# coreTwo.net
KiCad netlist of a schematic drawn in EAGLE
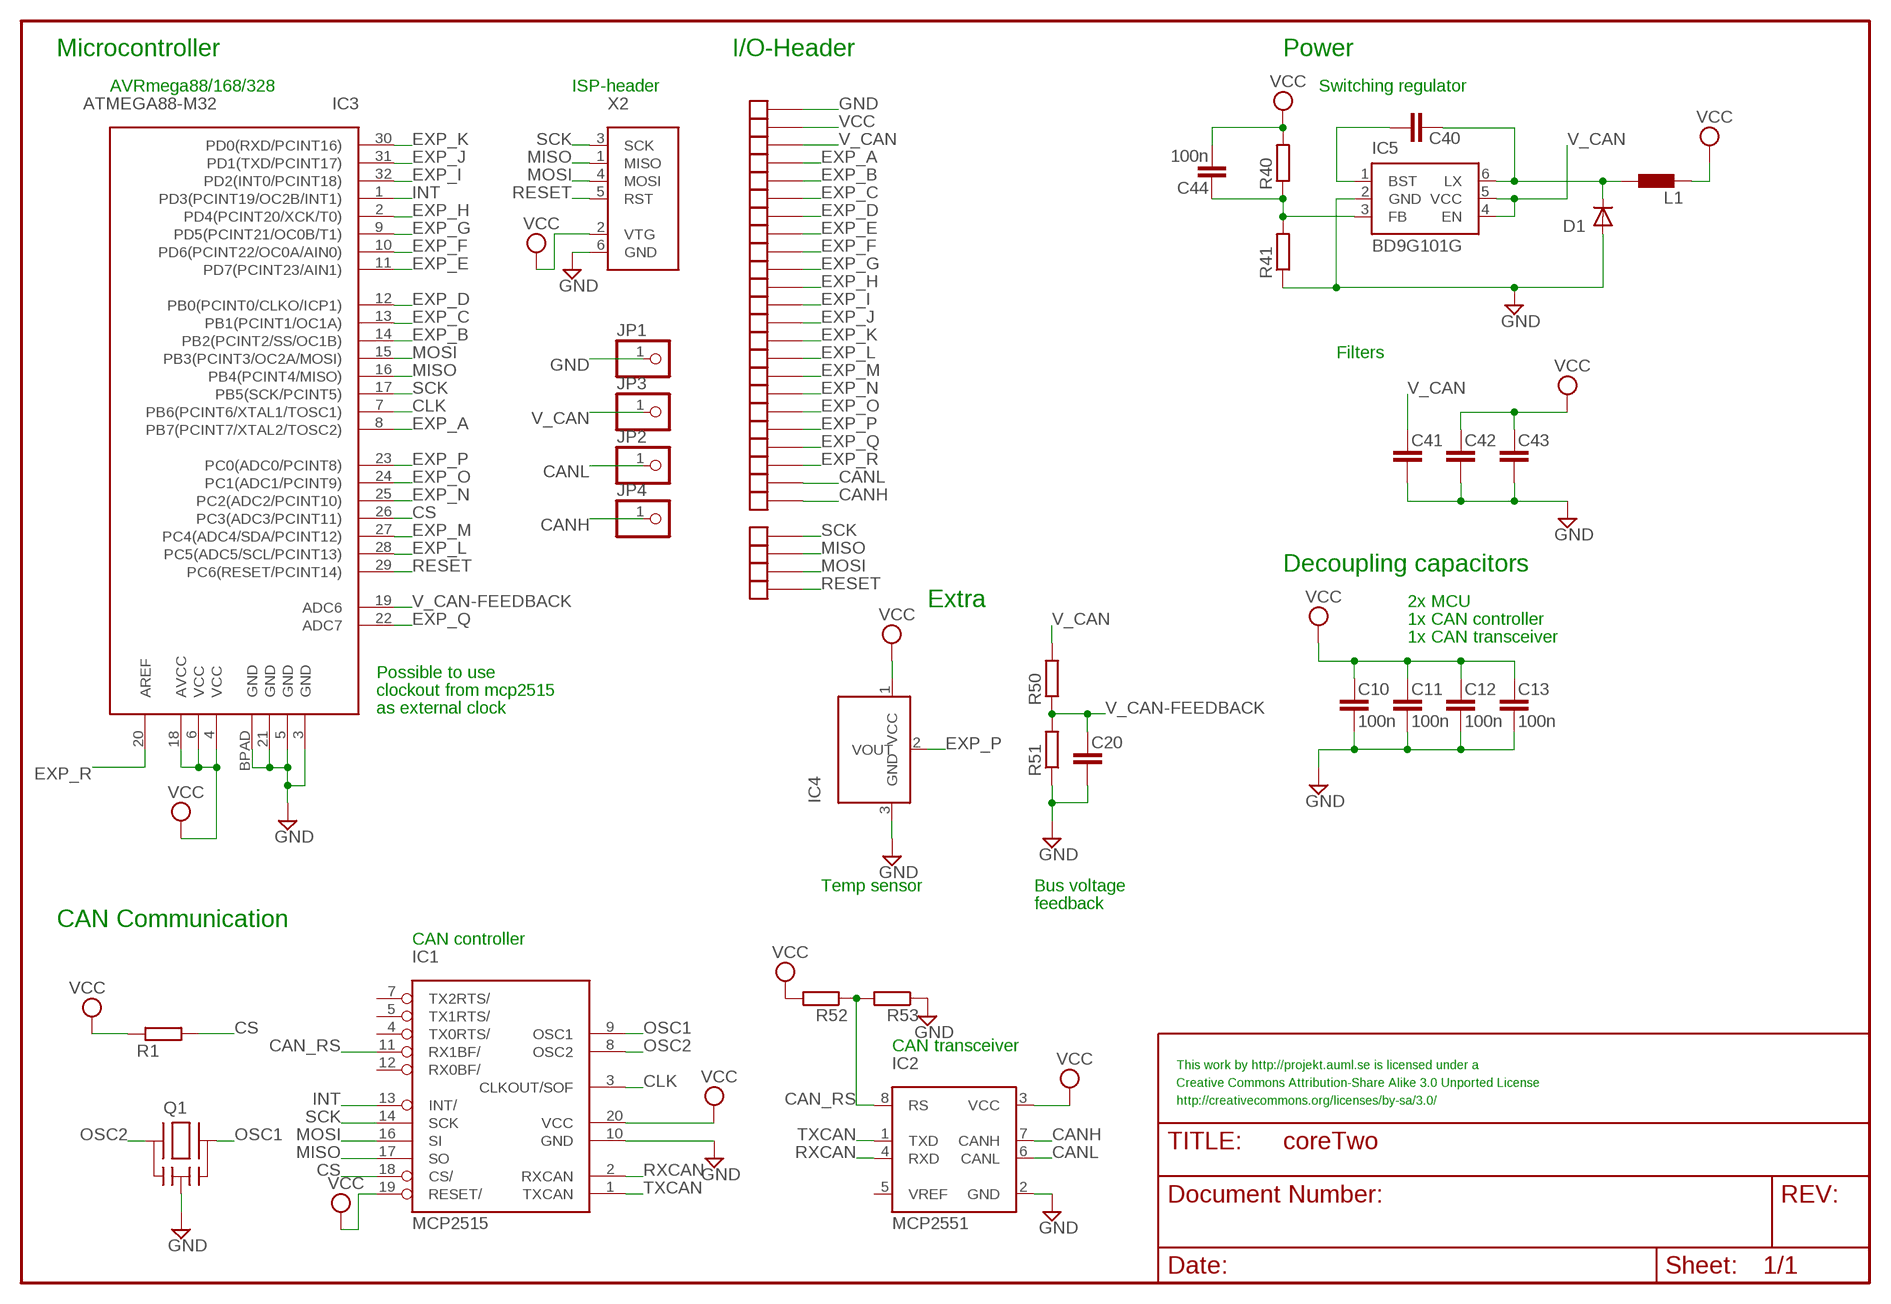
[diagram p0: schematic, sheet 1]

(export (version "E")
  (design (tool "Eeschema 10.0.6"))
  (components
    (comp (ref "C10")
      (value "100n")
      (footprint "eagle-import:C0402")
      (libsource (lib "eagle-import") (part "C-EUC0402"))
    )
    (comp (ref "C11")
      (value "100n")
      (footprint "eagle-import:C0402")
      (libsource (lib "eagle-import") (part "C-EUC0402"))
    )
    (comp (ref "C12")
      (value "100n")
      (footprint "eagle-import:C0402")
      (libsource (lib "eagle-import") (part "C-EUC0402"))
    )
    (comp (ref "C13")
      (value "100n")
      (footprint "eagle-import:C0402")
      (libsource (lib "eagle-import") (part "C-EUC0402"))
    )
    (comp (ref "C20")
      (value "C-EUC0402")
      (footprint "eagle-import:C0402")
      (libsource (lib "eagle-import") (part "C-EUC0402"))
    )
    (comp (ref "C40")
      (value "C-EUC0603")
      (footprint "eagle-import:C0603")
      (libsource (lib "eagle-import") (part "C-EUC0603"))
    )
    (comp (ref "C41")
      (value "C-EUC1210")
      (footprint "eagle-import:C1210")
      (libsource (lib "eagle-import") (part "C-EUC1210"))
    )
    (comp (ref "C42")
      (value "C-EUC0805")
      (footprint "eagle-import:C0805")
      (libsource (lib "eagle-import") (part "C-EUC0805"))
    )
    (comp (ref "C43")
      (value "C-EUC0402")
      (footprint "eagle-import:C0402")
      (libsource (lib "eagle-import") (part "C-EUC0402"))
    )
    (comp (ref "C44")
      (value "100n")
      (footprint "eagle-import:C0402")
      (libsource (lib "eagle-import") (part "C-EUC0402"))
    )
    (comp (ref "CANH")
      (value "CORETWO_PIN")
      (footprint "eagle-import:CORETWO_PIN")
      (libsource (lib "eagle-import") (part "CORETWO_PIN"))
    )
    (comp (ref "CANL")
      (value "CORETWO_PIN")
      (footprint "eagle-import:CORETWO_PIN")
      (libsource (lib "eagle-import") (part "CORETWO_PIN"))
    )
    (comp (ref "D1")
      (value "DIODESMP")
      (footprint "eagle-import:DO-220AA")
      (libsource (lib "eagle-import") (part "DIODESMP"))
    )
    (comp (ref "EXP_A")
      (value "CORETWO_PIN")
      (footprint "eagle-import:CORETWO_PIN")
      (libsource (lib "eagle-import") (part "CORETWO_PIN"))
    )
    (comp (ref "EXP_B")
      (value "CORETWO_PIN")
      (footprint "eagle-import:CORETWO_PIN")
      (libsource (lib "eagle-import") (part "CORETWO_PIN"))
    )
    (comp (ref "EXP_C")
      (value "CORETWO_PIN")
      (footprint "eagle-import:CORETWO_PIN")
      (libsource (lib "eagle-import") (part "CORETWO_PIN"))
    )
    (comp (ref "EXP_D")
      (value "CORETWO_PIN")
      (footprint "eagle-import:CORETWO_PIN")
      (libsource (lib "eagle-import") (part "CORETWO_PIN"))
    )
    (comp (ref "EXP_E")
      (value "CORETWO_PIN")
      (footprint "eagle-import:CORETWO_PIN")
      (libsource (lib "eagle-import") (part "CORETWO_PIN"))
    )
    (comp (ref "EXP_F")
      (value "CORETWO_PIN")
      (footprint "eagle-import:CORETWO_PIN")
      (libsource (lib "eagle-import") (part "CORETWO_PIN"))
    )
    (comp (ref "EXP_G")
      (value "CORETWO_PIN")
      (footprint "eagle-import:CORETWO_PIN")
      (libsource (lib "eagle-import") (part "CORETWO_PIN"))
    )
    (comp (ref "EXP_H")
      (value "CORETWO_PIN")
      (footprint "eagle-import:CORETWO_PIN")
      (libsource (lib "eagle-import") (part "CORETWO_PIN"))
    )
    (comp (ref "EXP_I")
      (value "CORETWO_PIN")
      (footprint "eagle-import:CORETWO_PIN")
      (libsource (lib "eagle-import") (part "CORETWO_PIN"))
    )
    (comp (ref "EXP_J")
      (value "CORETWO_PIN")
      (footprint "eagle-import:CORETWO_PIN")
      (libsource (lib "eagle-import") (part "CORETWO_PIN"))
    )
    (comp (ref "EXP_K")
      (value "CORETWO_PIN")
      (footprint "eagle-import:CORETWO_PIN")
      (libsource (lib "eagle-import") (part "CORETWO_PIN"))
    )
    (comp (ref "EXP_L")
      (value "CORETWO_PIN")
      (footprint "eagle-import:CORETWO_PIN")
      (libsource (lib "eagle-import") (part "CORETWO_PIN"))
    )
    (comp (ref "EXP_M")
      (value "CORETWO_PIN")
      (footprint "eagle-import:CORETWO_PIN")
      (libsource (lib "eagle-import") (part "CORETWO_PIN"))
    )
    (comp (ref "EXP_N")
      (value "CORETWO_PIN")
      (footprint "eagle-import:CORETWO_PIN")
      (libsource (lib "eagle-import") (part "CORETWO_PIN"))
    )
    (comp (ref "EXP_O")
      (value "CORETWO_PIN")
      (footprint "eagle-import:CORETWO_PIN")
      (libsource (lib "eagle-import") (part "CORETWO_PIN"))
    )
    (comp (ref "EXP_P")
      (value "CORETWO_PIN")
      (footprint "eagle-import:CORETWO_PIN")
      (libsource (lib "eagle-import") (part "CORETWO_PIN"))
    )
    (comp (ref "EXP_Q")
      (value "CORETWO_PIN")
      (footprint "eagle-import:CORETWO_PIN")
      (libsource (lib "eagle-import") (part "CORETWO_PIN"))
    )
    (comp (ref "EXP_R")
      (value "CORETWO_PIN")
      (footprint "eagle-import:CORETWO_PIN")
      (libsource (lib "eagle-import") (part "CORETWO_PIN"))
    )
    (comp (ref "GND")
      (value "CORETWO_PIN")
      (footprint "eagle-import:CORETWO_PIN")
      (libsource (lib "eagle-import") (part "CORETWO_PIN"))
    )
    (comp (ref "IC1")
      (value "MCP2515")
      (footprint "eagle-import:TSSOP")
      (libsource (lib "eagle-import") (part "MCP2515"))
    )
    (comp (ref "IC2")
      (value "MCP2551")
      (footprint "eagle-import:SOIC")
      (libsource (lib "eagle-import") (part "MCP2551"))
    )
    (comp (ref "IC3")
      (value "ATMEGA88-M32")
      (footprint "eagle-import:MLF32")
      (libsource (lib "eagle-import") (part "ATMEGA88-M32"))
    )
    (comp (ref "IC4")
      (value "TC1047A")
      (footprint "eagle-import:SOT23")
      (libsource (lib "eagle-import") (part "TC1047A"))
    )
    (comp (ref "IC5")
      (value "BD9G101G")
      (footprint "eagle-import:SSOP6")
      (libsource (lib "eagle-import") (part "BD9G101G"))
    )
    (comp (ref "JP1")
      (value "PINHD-1X1SMD")
      (footprint "eagle-import:1X01_SMD")
      (libsource (lib "eagle-import") (part "PINHD-1X1SMD"))
    )
    (comp (ref "JP2")
      (value "PINHD-1X1SMD")
      (footprint "eagle-import:1X01_SMD")
      (libsource (lib "eagle-import") (part "PINHD-1X1SMD"))
    )
    (comp (ref "JP3")
      (value "PINHD-1X1SMD")
      (footprint "eagle-import:1X01_SMD")
      (libsource (lib "eagle-import") (part "PINHD-1X1SMD"))
    )
    (comp (ref "JP4")
      (value "PINHD-1X1SMD")
      (footprint "eagle-import:1X01_SMD")
      (libsource (lib "eagle-import") (part "PINHD-1X1SMD"))
    )
    (comp (ref "L1")
      (value "L-EUL1210")
      (footprint "eagle-import:L1210")
      (libsource (lib "eagle-import") (part "L-EUL1210"))
    )
    (comp (ref "MISO")
      (value "CORETWO_PIN")
      (footprint "eagle-import:CORETWO_PIN")
      (libsource (lib "eagle-import") (part "CORETWO_PIN"))
    )
    (comp (ref "MOSI")
      (value "CORETWO_PIN")
      (footprint "eagle-import:CORETWO_PIN")
      (libsource (lib "eagle-import") (part "CORETWO_PIN"))
    )
    (comp (ref "Q1")
      (value "CSTCESMD")
      (footprint "eagle-import:SMD")
      (libsource (lib "eagle-import") (part "CSTCESMD"))
    )
    (comp (ref "R1")
      (value "R-EUR0402")
      (footprint "eagle-import:R0402")
      (libsource (lib "eagle-import") (part "R-EUR0402"))
    )
    (comp (ref "R40")
      (value "R-EUR0402")
      (footprint "eagle-import:R0402")
      (libsource (lib "eagle-import") (part "R-EUR0402"))
    )
    (comp (ref "R41")
      (value "R-EUR0402")
      (footprint "eagle-import:R0402")
      (libsource (lib "eagle-import") (part "R-EUR0402"))
    )
    (comp (ref "R50")
      (value "R-EUR0402")
      (footprint "eagle-import:R0402")
      (libsource (lib "eagle-import") (part "R-EUR0402"))
    )
    (comp (ref "R51")
      (value "R-EUR0402")
      (footprint "eagle-import:R0402")
      (libsource (lib "eagle-import") (part "R-EUR0402"))
    )
    (comp (ref "R52")
      (value "R-EUR0402")
      (footprint "eagle-import:R0402")
      (libsource (lib "eagle-import") (part "R-EUR0402"))
    )
    (comp (ref "R53")
      (value "R-EUR0402")
      (footprint "eagle-import:R0402")
      (libsource (lib "eagle-import") (part "R-EUR0402"))
    )
    (comp (ref "RST")
      (value "CORETWO_PIN")
      (footprint "eagle-import:CORETWO_PIN")
      (libsource (lib "eagle-import") (part "CORETWO_PIN"))
    )
    (comp (ref "SCK")
      (value "CORETWO_PIN")
      (footprint "eagle-import:CORETWO_PIN")
      (libsource (lib "eagle-import") (part "CORETWO_PIN"))
    )
    (comp (ref "VCC")
      (value "CORETWO_PIN")
      (footprint "eagle-import:CORETWO_PIN")
      (libsource (lib "eagle-import") (part "CORETWO_PIN"))
    )
    (comp (ref "V_CAN")
      (value "CORETWO_PIN")
      (footprint "eagle-import:CORETWO_PIN")
      (libsource (lib "eagle-import") (part "CORETWO_PIN"))
    )
    (comp (ref "X2")
      (value "AVRISP6PIN")
      (footprint "eagle-import:6PINSMD")
      (libsource (lib "eagle-import") (part "AVRISP6PIN"))
    )
  )
  (nets
    (net (code "1") (name "/CANH") (class "Default")
      (node (ref "CANH") (pin "1") (pinfunction "EXP__1") (pintype "bidirectional"))
      (node (ref "IC2") (pin "7") (pinfunction "CANH_7") (pintype "bidirectional"))
      (node (ref "JP4") (pin "1") (pinfunction "1_1") (pintype "passive"))
    )
    (net (code "2") (name "/CANL") (class "Default")
      (node (ref "CANL") (pin "1") (pinfunction "EXP__1") (pintype "bidirectional"))
      (node (ref "IC2") (pin "6") (pinfunction "CANL_6") (pintype "bidirectional"))
      (node (ref "JP2") (pin "1") (pinfunction "1_1") (pintype "passive"))
    )
    (net (code "3") (name "/CAN_RS") (class "Default")
      (node (ref "IC1") (pin "11") (pinfunction "RX1BF/_11") (pintype "bidirectional"))
      (node (ref "IC2") (pin "8") (pinfunction "RS_8") (pintype "bidirectional"))
      (node (ref "R52") (pin "1") (pinfunction "1_1") (pintype "passive"))
      (node (ref "R53") (pin "2") (pinfunction "2_2") (pintype "passive"))
    )
    (net (code "4") (name "/CLK") (class "Default")
      (node (ref "IC1") (pin "3") (pinfunction "CLKOUT/SOF_3") (pintype "bidirectional"))
      (node (ref "IC3") (pin "7") (pinfunction "PB6(PCINT6/XTAL1/TOSC1)_7") (pintype "bidirectional"))
    )
    (net (code "5") (name "/CS") (class "Default")
      (node (ref "IC1") (pin "18") (pinfunction "CS/_18") (pintype "input"))
      (node (ref "IC3") (pin "26") (pinfunction "PC3(ADC3/PCINT11)_26") (pintype "bidirectional"))
      (node (ref "R1") (pin "2") (pinfunction "2_2") (pintype "passive"))
    )
    (net (code "6") (name "/EXP_A") (class "Default")
      (node (ref "EXP_A") (pin "1") (pinfunction "EXP__1") (pintype "bidirectional"))
      (node (ref "IC3") (pin "8") (pinfunction "PB7(PCINT7/XTAL2/TOSC2)_8") (pintype "bidirectional"))
    )
    (net (code "7") (name "/EXP_B") (class "Default")
      (node (ref "EXP_B") (pin "1") (pinfunction "EXP__1") (pintype "bidirectional"))
      (node (ref "IC3") (pin "14") (pinfunction "PB2(PCINT2/SS/OC1B)_14") (pintype "bidirectional"))
    )
    (net (code "8") (name "/EXP_C") (class "Default")
      (node (ref "EXP_C") (pin "1") (pinfunction "EXP__1") (pintype "bidirectional"))
      (node (ref "IC3") (pin "13") (pinfunction "PB1(PCINT1/OC1A)_13") (pintype "bidirectional"))
    )
    (net (code "9") (name "/EXP_D") (class "Default")
      (node (ref "EXP_D") (pin "1") (pinfunction "EXP__1") (pintype "bidirectional"))
      (node (ref "IC3") (pin "12") (pinfunction "PB0(PCINT0/CLKO/ICP1)_12") (pintype "bidirectional"))
    )
    (net (code "10") (name "/EXP_E") (class "Default")
      (node (ref "EXP_E") (pin "1") (pinfunction "EXP__1") (pintype "bidirectional"))
      (node (ref "IC3") (pin "11") (pinfunction "PD7(PCINT23/AIN1)_11") (pintype "bidirectional"))
    )
    (net (code "11") (name "/EXP_F") (class "Default")
      (node (ref "EXP_F") (pin "1") (pinfunction "EXP__1") (pintype "bidirectional"))
      (node (ref "IC3") (pin "10") (pinfunction "PD6(PCINT22/OC0A/AIN0)_10") (pintype "bidirectional"))
    )
    (net (code "12") (name "/EXP_G") (class "Default")
      (node (ref "EXP_G") (pin "1") (pinfunction "EXP__1") (pintype "bidirectional"))
      (node (ref "IC3") (pin "9") (pinfunction "PD5(PCINT21/OC0B/T1)_9") (pintype "bidirectional"))
    )
    (net (code "13") (name "/EXP_H") (class "Default")
      (node (ref "EXP_H") (pin "1") (pinfunction "EXP__1") (pintype "bidirectional"))
      (node (ref "IC3") (pin "2") (pinfunction "PD4(PCINT20/XCK/T0)_2") (pintype "bidirectional"))
    )
    (net (code "14") (name "/EXP_I") (class "Default")
      (node (ref "EXP_I") (pin "1") (pinfunction "EXP__1") (pintype "bidirectional"))
      (node (ref "IC3") (pin "32") (pinfunction "PD2(INT0/PCINT18)_32") (pintype "bidirectional"))
    )
    (net (code "15") (name "/EXP_J") (class "Default")
      (node (ref "EXP_J") (pin "1") (pinfunction "EXP__1") (pintype "bidirectional"))
      (node (ref "IC3") (pin "31") (pinfunction "PD1(TXD/PCINT17)_31") (pintype "bidirectional"))
    )
    (net (code "16") (name "/EXP_K") (class "Default")
      (node (ref "EXP_K") (pin "1") (pinfunction "EXP__1") (pintype "bidirectional"))
      (node (ref "IC3") (pin "30") (pinfunction "PD0(RXD/PCINT16)_30") (pintype "bidirectional"))
    )
    (net (code "17") (name "/EXP_L") (class "Default")
      (node (ref "EXP_L") (pin "1") (pinfunction "EXP__1") (pintype "bidirectional"))
      (node (ref "IC3") (pin "28") (pinfunction "PC5(ADC5/SCL/PCINT13)_28") (pintype "bidirectional"))
    )
    (net (code "18") (name "/EXP_M") (class "Default")
      (node (ref "EXP_M") (pin "1") (pinfunction "EXP__1") (pintype "bidirectional"))
      (node (ref "IC3") (pin "27") (pinfunction "PC4(ADC4/SDA/PCINT12)_27") (pintype "bidirectional"))
    )
    (net (code "19") (name "/EXP_N") (class "Default")
      (node (ref "EXP_N") (pin "1") (pinfunction "EXP__1") (pintype "bidirectional"))
      (node (ref "IC3") (pin "25") (pinfunction "PC2(ADC2/PCINT10)_25") (pintype "bidirectional"))
    )
    (net (code "20") (name "/EXP_O") (class "Default")
      (node (ref "EXP_O") (pin "1") (pinfunction "EXP__1") (pintype "bidirectional"))
      (node (ref "IC3") (pin "24") (pinfunction "PC1(ADC1/PCINT9)_24") (pintype "bidirectional"))
    )
    (net (code "21") (name "/EXP_P") (class "Default")
      (node (ref "EXP_P") (pin "1") (pinfunction "EXP__1") (pintype "bidirectional"))
      (node (ref "IC3") (pin "23") (pinfunction "PC0(ADC0/PCINT8)_23") (pintype "bidirectional"))
      (node (ref "IC4") (pin "2") (pinfunction "VOUT_2") (pintype "output"))
    )
    (net (code "22") (name "/EXP_Q") (class "Default")
      (node (ref "EXP_Q") (pin "1") (pinfunction "EXP__1") (pintype "bidirectional"))
      (node (ref "IC3") (pin "22") (pinfunction "ADC7_22") (pintype "bidirectional"))
    )
    (net (code "23") (name "/EXP_R") (class "Default")
      (node (ref "EXP_R") (pin "1") (pinfunction "EXP__1") (pintype "bidirectional"))
      (node (ref "IC3") (pin "20") (pinfunction "AREF_20") (pintype "passive"))
    )
    (net (code "24") (name "/INT") (class "Default")
      (node (ref "IC1") (pin "13") (pinfunction "INT/_13") (pintype "output"))
      (node (ref "IC3") (pin "1") (pinfunction "PD3(PCINT19/OC2B/INT1)_1") (pintype "bidirectional"))
    )
    (net (code "25") (name "/MISO") (class "Default")
      (node (ref "IC1") (pin "17") (pinfunction "SO_17") (pintype "output"))
      (node (ref "IC3") (pin "16") (pinfunction "PB4(PCINT4/MISO)_16") (pintype "bidirectional"))
      (node (ref "MISO") (pin "1") (pinfunction "EXP__1") (pintype "bidirectional"))
      (node (ref "X2") (pin "1") (pinfunction "MISO_1") (pintype "bidirectional"))
    )
    (net (code "26") (name "/MOSI") (class "Default")
      (node (ref "IC1") (pin "16") (pinfunction "SI_16") (pintype "input"))
      (node (ref "IC3") (pin "15") (pinfunction "PB3(PCINT3/OC2A/MOSI)_15") (pintype "bidirectional"))
      (node (ref "MOSI") (pin "1") (pinfunction "EXP__1") (pintype "bidirectional"))
      (node (ref "X2") (pin "4") (pinfunction "MOSI_4") (pintype "bidirectional"))
    )
    (net (code "27") (name "/OSC1") (class "Default")
      (node (ref "IC1") (pin "9") (pinfunction "OSC1_9") (pintype "bidirectional"))
      (node (ref "Q1") (pin "3") (pinfunction "2_3") (pintype "bidirectional"))
    )
    (net (code "28") (name "/OSC2") (class "Default")
      (node (ref "IC1") (pin "8") (pinfunction "OSC2_8") (pintype "bidirectional"))
      (node (ref "Q1") (pin "1") (pinfunction "1_1") (pintype "bidirectional"))
    )
    (net (code "29") (name "/RESET") (class "Default")
      (node (ref "IC3") (pin "29") (pinfunction "PC6(RESET/PCINT14)_29") (pintype "bidirectional"))
      (node (ref "RST") (pin "1") (pinfunction "EXP__1") (pintype "bidirectional"))
      (node (ref "X2") (pin "5") (pinfunction "RST_5") (pintype "bidirectional"))
    )
    (net (code "30") (name "/RXCAN") (class "Default")
      (node (ref "IC1") (pin "2") (pinfunction "RXCAN_2") (pintype "bidirectional"))
      (node (ref "IC2") (pin "4") (pinfunction "RXD_4") (pintype "bidirectional"))
    )
    (net (code "31") (name "/SCK") (class "Default")
      (node (ref "IC1") (pin "14") (pinfunction "SCK_14") (pintype "input"))
      (node (ref "IC3") (pin "17") (pinfunction "PB5(SCK/PCINT5)_17") (pintype "bidirectional"))
      (node (ref "SCK") (pin "1") (pinfunction "EXP__1") (pintype "bidirectional"))
      (node (ref "X2") (pin "3") (pinfunction "SCK_3") (pintype "bidirectional"))
    )
    (net (code "32") (name "/TXCAN") (class "Default")
      (node (ref "IC1") (pin "1") (pinfunction "TXCAN_1") (pintype "bidirectional"))
      (node (ref "IC2") (pin "1") (pinfunction "TXD_1") (pintype "bidirectional"))
    )
    (net (code "33") (name "/V_CAN") (class "Default")
      (node (ref "C41") (pin "1") (pinfunction "1_1") (pintype "passive"))
      (node (ref "IC5") (pin "4") (pinfunction "EN_4") (pintype "bidirectional"))
      (node (ref "IC5") (pin "5") (pinfunction "VCC_5") (pintype "bidirectional"))
      (node (ref "JP3") (pin "1") (pinfunction "1_1") (pintype "passive"))
      (node (ref "R50") (pin "2") (pinfunction "2_2") (pintype "passive"))
      (node (ref "V_CAN") (pin "1") (pinfunction "EXP__1") (pintype "bidirectional"))
    )
    (net (code "34") (name "/V_CAN-FEEDBACK") (class "Default")
      (node (ref "C20") (pin "1") (pinfunction "1_1") (pintype "passive"))
      (node (ref "IC3") (pin "19") (pinfunction "ADC6_19") (pintype "bidirectional"))
      (node (ref "R50") (pin "1") (pinfunction "1_1") (pintype "passive"))
      (node (ref "R51") (pin "2") (pinfunction "2_2") (pintype "passive"))
    )
    (net (code "35") (name "GND") (class "Default")
      (node (ref "C10") (pin "2") (pinfunction "2_2") (pintype "passive"))
      (node (ref "C11") (pin "2") (pinfunction "2_2") (pintype "passive"))
      (node (ref "C12") (pin "2") (pinfunction "2_2") (pintype "passive"))
      (node (ref "C13") (pin "2") (pinfunction "2_2") (pintype "passive"))
      (node (ref "C20") (pin "2") (pinfunction "2_2") (pintype "passive"))
      (node (ref "C41") (pin "2") (pinfunction "2_2") (pintype "passive"))
      (node (ref "C42") (pin "2") (pinfunction "2_2") (pintype "passive"))
      (node (ref "C43") (pin "2") (pinfunction "2_2") (pintype "passive"))
      (node (ref "D1") (pin "A") (pinfunction "A_A") (pintype "passive"))
      (node (ref "GND") (pin "1") (pinfunction "EXP__1") (pintype "bidirectional"))
      (node (ref "IC1") (pin "10") (pinfunction "GND_10") (pintype "power_in"))
      (node (ref "IC2") (pin "2") (pinfunction "GND_2") (pintype "power_in"))
      (node (ref "IC3") (pin "21") (pinfunction "GND_21") (pintype "power_in"))
      (node (ref "IC3") (pin "3") (pinfunction "GND_3") (pintype "power_in"))
      (node (ref "IC3") (pin "5") (pinfunction "GND_5") (pintype "power_in"))
      (node (ref "IC3") (pin "BPAD") (pinfunction "GND_BPAD") (pintype "power_in"))
      (node (ref "IC4") (pin "3") (pinfunction "GND_3") (pintype "power_in"))
      (node (ref "IC5") (pin "2") (pinfunction "GND_2") (pintype "bidirectional"))
      (node (ref "JP1") (pin "1") (pinfunction "1_1") (pintype "passive"))
      (node (ref "Q1") (pin "2") (pinfunction "GND_2") (pintype "bidirectional"))
      (node (ref "R41") (pin "1") (pinfunction "1_1") (pintype "passive"))
      (node (ref "R51") (pin "1") (pinfunction "1_1") (pintype "passive"))
      (node (ref "R53") (pin "1") (pinfunction "1_1") (pintype "passive"))
      (node (ref "X2") (pin "6") (pinfunction "GND_6") (pintype "bidirectional"))
    )
    (net (code "36") (name "Net-(IC5-BST)") (class "Default")
      (node (ref "C40") (pin "1") (pinfunction "1_1") (pintype "passive"))
      (node (ref "IC5") (pin "1") (pinfunction "BST_1") (pintype "bidirectional"))
    )
    (net (code "37") (name "Net-(IC5-FB)") (class "Default")
      (node (ref "C44") (pin "1") (pinfunction "1_1") (pintype "passive"))
      (node (ref "IC5") (pin "3") (pinfunction "FB_3") (pintype "bidirectional"))
      (node (ref "R40") (pin "1") (pinfunction "1_1") (pintype "passive"))
      (node (ref "R41") (pin "2") (pinfunction "2_2") (pintype "passive"))
    )
    (net (code "38") (name "Net-(IC5-LX)") (class "Default")
      (node (ref "C40") (pin "2") (pinfunction "2_2") (pintype "passive"))
      (node (ref "D1") (pin "C") (pinfunction "C_C") (pintype "passive"))
      (node (ref "IC5") (pin "6") (pinfunction "LX_6") (pintype "bidirectional"))
      (node (ref "L1") (pin "2") (pinfunction "P$2_2") (pintype "passive"))
    )
    (net (code "39") (name "VCC") (class "Default")
      (node (ref "C10") (pin "1") (pinfunction "1_1") (pintype "passive"))
      (node (ref "C11") (pin "1") (pinfunction "1_1") (pintype "passive"))
      (node (ref "C12") (pin "1") (pinfunction "1_1") (pintype "passive"))
      (node (ref "C13") (pin "1") (pinfunction "1_1") (pintype "passive"))
      (node (ref "C42") (pin "1") (pinfunction "1_1") (pintype "passive"))
      (node (ref "C43") (pin "1") (pinfunction "1_1") (pintype "passive"))
      (node (ref "C44") (pin "2") (pinfunction "2_2") (pintype "passive"))
      (node (ref "IC1") (pin "19") (pinfunction "RESET/_19") (pintype "input"))
      (node (ref "IC1") (pin "20") (pinfunction "VCC_20") (pintype "power_in"))
      (node (ref "IC2") (pin "3") (pinfunction "VCC_3") (pintype "power_in"))
      (node (ref "IC3") (pin "18") (pinfunction "AVCC_18") (pintype "power_in"))
      (node (ref "IC3") (pin "4") (pinfunction "VCC_4") (pintype "power_in"))
      (node (ref "IC3") (pin "6") (pinfunction "VCC_6") (pintype "power_in"))
      (node (ref "IC4") (pin "1") (pinfunction "VCC_1") (pintype "power_in"))
      (node (ref "L1") (pin "1") (pinfunction "P$1_1") (pintype "passive"))
      (node (ref "R1") (pin "1") (pinfunction "1_1") (pintype "passive"))
      (node (ref "R40") (pin "2") (pinfunction "2_2") (pintype "passive"))
      (node (ref "R52") (pin "2") (pinfunction "2_2") (pintype "passive"))
      (node (ref "VCC") (pin "1") (pinfunction "EXP__1") (pintype "bidirectional"))
      (node (ref "X2") (pin "2") (pinfunction "VTG_2") (pintype "bidirectional"))
    )
    (net (code "40") (name "unconnected-(IC1-RX0BF{slash}-Pad12)") (class "Default")
      (node (ref "IC1") (pin "12") (pinfunction "RX0BF/_12") (pintype "bidirectional"))
    )
    (net (code "41") (name "unconnected-(IC1-TX0RTS{slash}-Pad4)") (class "Default")
      (node (ref "IC1") (pin "4") (pinfunction "TX0RTS/_4") (pintype "bidirectional"))
    )
    (net (code "42") (name "unconnected-(IC1-TX1RTS{slash}-Pad5)") (class "Default")
      (node (ref "IC1") (pin "5") (pinfunction "TX1RTS/_5") (pintype "bidirectional"))
    )
    (net (code "43") (name "unconnected-(IC1-TX2RTS{slash}-Pad7)") (class "Default")
      (node (ref "IC1") (pin "7") (pinfunction "TX2RTS/_7") (pintype "bidirectional"))
    )
    (net (code "44") (name "unconnected-(IC2-VREF-Pad5)") (class "Default")
      (node (ref "IC2") (pin "5") (pinfunction "VREF_5") (pintype "bidirectional"))
    )
  )
)
